# Peripherals.net
KiCad netlist of a schematic drawn in Altium Designer
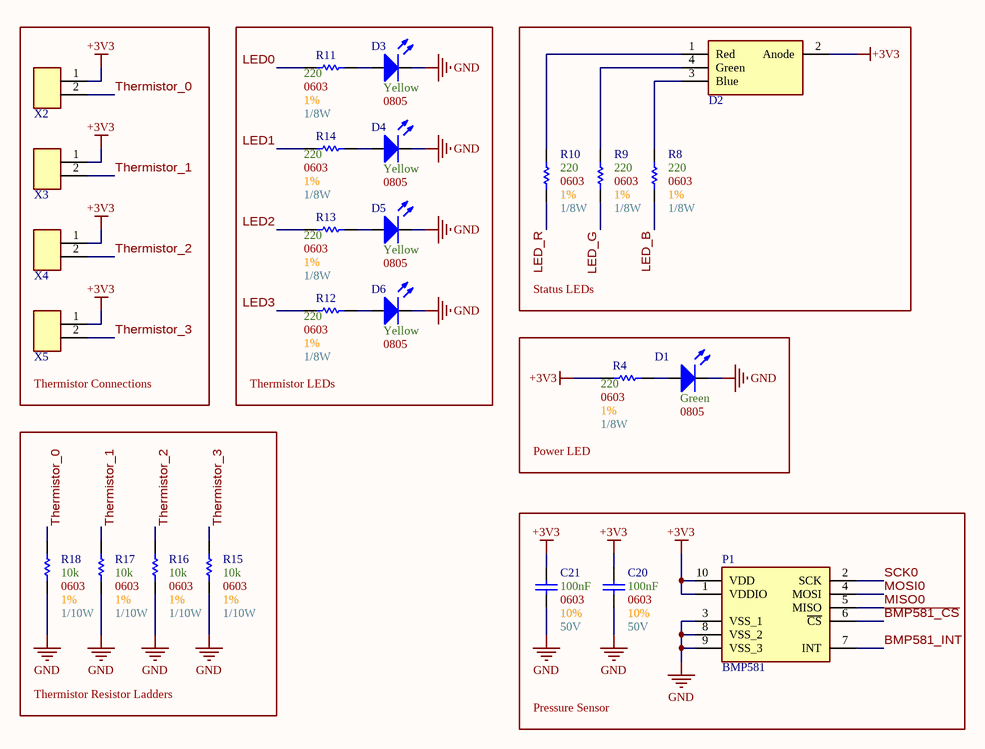
[diagram p0: Peripherals.SchDoc]

(export (version "E")
  (design (tool "Eeschema 10.0.6"))
  (components
    (comp (ref "C20")
      (value "[Cap] 0603 0.1uF 10% 50V")
      (footprint "[Cap] SMD 0603")
      (description "CL10B104KB8NNNC")
      (fields
        (field (name "MAX VOLTAGE") "50V")
        (field (name "SIZE PACKAGE") "0603")
        (field (name "TOLERANCE") "10%")
        (field (name "CAPACITANCE") "100nF")
      )
      (libsource (lib "Capacitors") (part "[Cap] 0603 0.1uF 10% 50V"))
    )
    (comp (ref "C21")
      (value "[Cap] 0603 0.1uF 10% 50V")
      (footprint "[Cap] SMD 0603")
      (description "CL10B104KB8NNNC")
      (fields
        (field (name "MAX VOLTAGE") "50V")
        (field (name "SIZE PACKAGE") "0603")
        (field (name "TOLERANCE") "10%")
        (field (name "CAPACITANCE") "100nF")
      )
      (libsource (lib "Capacitors") (part "[Cap] 0603 0.1uF 10% 50V"))
    )
    (comp (ref "D1")
      (value "[LED] SMD 0805 Green")
      (footprint "[LED] SMD 0805")
      (description "LG R971-KN-1-0-20-R18")
      (fields (field (name "COLOR") "Green") (field (name "SIZE PACKAGE") "0805"))
      (libsource (lib "LEDs") (part "[LED] SMD 0805 Green"))
    )
    (comp (ref "D2")
      (value "[LED] SMD RGB 1.55x1.55mm")
      (footprint "[LED] SMD RGB 1.55x1.55mm")
      (description "LTST-E143EGBW-P1")
      (libsource (lib "LEDs") (part "[LED] SMD RGB 1.55x1.55mm"))
    )
    (comp (ref "D3")
      (value "[LED] SMD 0805 Yellow")
      (footprint "[LED] SMD 0805")
      (description "LY R976-PS-36-0-20-R18")
      (fields (field (name "COLOR") "Yellow") (field (name "SIZE PACKAGE") "0805"))
      (libsource (lib "LEDs") (part "[LED] SMD 0805 Yellow"))
    )
    (comp (ref "D4")
      (value "[LED] SMD 0805 Yellow")
      (footprint "[LED] SMD 0805")
      (description "LY R976-PS-36-0-20-R18")
      (fields (field (name "COLOR") "Yellow") (field (name "SIZE PACKAGE") "0805"))
      (libsource (lib "LEDs") (part "[LED] SMD 0805 Yellow"))
    )
    (comp (ref "D5")
      (value "[LED] SMD 0805 Yellow")
      (footprint "[LED] SMD 0805")
      (description "LY R976-PS-36-0-20-R18")
      (fields (field (name "COLOR") "Yellow") (field (name "SIZE PACKAGE") "0805"))
      (libsource (lib "LEDs") (part "[LED] SMD 0805 Yellow"))
    )
    (comp (ref "D6")
      (value "[LED] SMD 0805 Yellow")
      (footprint "[LED] SMD 0805")
      (description "LY R976-PS-36-0-20-R18")
      (fields (field (name "COLOR") "Yellow") (field (name "SIZE PACKAGE") "0805"))
      (libsource (lib "LEDs") (part "[LED] SMD 0805 Yellow"))
    )
    (comp (ref "P1")
      (value "BMP581")
      (footprint "[Sensor] Barometric Pressure Sensor")
      (libsource (lib "ICs") (part "[Sensor] Barometric Pressure Sensor"))
    )
    (comp (ref "R4")
      (value "[220] SMD 0603 1% 1/10W")
      (footprint "[Res] SMD 0603")
      (description "CRGCQ0805F220R")
      (fields
        (field (name "WATTAGE") "1/8W")
        (field (name "TOLERANCE") "1%")
        (field (name "RESISTANCE") "220")
        (field (name "SIZE PACKAGE") "0603")
      )
      (libsource (lib "Resistors") (part "[220] SMD 0603 1% 1/10W"))
    )
    (comp (ref "R8")
      (value "[220] SMD 0603 1% 1/10W")
      (footprint "[Res] SMD 0603")
      (description "CRGCQ0805F220R")
      (fields
        (field (name "WATTAGE") "1/8W")
        (field (name "TOLERANCE") "1%")
        (field (name "RESISTANCE") "220")
        (field (name "SIZE PACKAGE") "0603")
      )
      (libsource (lib "Resistors") (part "[220] SMD 0603 1% 1/10W"))
    )
    (comp (ref "R9")
      (value "[220] SMD 0603 1% 1/10W")
      (footprint "[Res] SMD 0603")
      (description "CRGCQ0805F220R")
      (fields
        (field (name "WATTAGE") "1/8W")
        (field (name "TOLERANCE") "1%")
        (field (name "RESISTANCE") "220")
        (field (name "SIZE PACKAGE") "0603")
      )
      (libsource (lib "Resistors") (part "[220] SMD 0603 1% 1/10W"))
    )
    (comp (ref "R10")
      (value "[220] SMD 0603 1% 1/10W")
      (footprint "[Res] SMD 0603")
      (description "CRGCQ0805F220R")
      (fields
        (field (name "WATTAGE") "1/8W")
        (field (name "TOLERANCE") "1%")
        (field (name "RESISTANCE") "220")
        (field (name "SIZE PACKAGE") "0603")
      )
      (libsource (lib "Resistors") (part "[220] SMD 0603 1% 1/10W"))
    )
    (comp (ref "R11")
      (value "[220] SMD 0603 1% 1/10W")
      (footprint "[Res] SMD 0603")
      (description "CRGCQ0805F220R")
      (fields
        (field (name "WATTAGE") "1/8W")
        (field (name "TOLERANCE") "1%")
        (field (name "RESISTANCE") "220")
        (field (name "SIZE PACKAGE") "0603")
      )
      (libsource (lib "Resistors") (part "[220] SMD 0603 1% 1/10W"))
    )
    (comp (ref "R12")
      (value "[220] SMD 0603 1% 1/10W")
      (footprint "[Res] SMD 0603")
      (description "CRGCQ0805F220R")
      (fields
        (field (name "WATTAGE") "1/8W")
        (field (name "TOLERANCE") "1%")
        (field (name "RESISTANCE") "220")
        (field (name "SIZE PACKAGE") "0603")
      )
      (libsource (lib "Resistors") (part "[220] SMD 0603 1% 1/10W"))
    )
    (comp (ref "R13")
      (value "[220] SMD 0603 1% 1/10W")
      (footprint "[Res] SMD 0603")
      (description "CRGCQ0805F220R")
      (fields
        (field (name "WATTAGE") "1/8W")
        (field (name "TOLERANCE") "1%")
        (field (name "RESISTANCE") "220")
        (field (name "SIZE PACKAGE") "0603")
      )
      (libsource (lib "Resistors") (part "[220] SMD 0603 1% 1/10W"))
    )
    (comp (ref "R14")
      (value "[220] SMD 0603 1% 1/10W")
      (footprint "[Res] SMD 0603")
      (description "CRGCQ0805F220R")
      (fields
        (field (name "WATTAGE") "1/8W")
        (field (name "TOLERANCE") "1%")
        (field (name "RESISTANCE") "220")
        (field (name "SIZE PACKAGE") "0603")
      )
      (libsource (lib "Resistors") (part "[220] SMD 0603 1% 1/10W"))
    )
    (comp (ref "R15")
      (value "[10k] SMD 0603 1% 1/8W")
      (footprint "[Res] SMD 0603")
      (description "RMCF0603FT10K0")
      (fields
        (field (name "WATTAGE") "1/10W")
        (field (name "TOLERANCE") "1%")
        (field (name "RESISTANCE") "10k")
        (field (name "SIZE PACKAGE") "0603")
      )
      (libsource (lib "Resistors") (part "[10k] SMD 0603 1% 1/8W"))
    )
    (comp (ref "R16")
      (value "[10k] SMD 0603 1% 1/8W")
      (footprint "[Res] SMD 0603")
      (description "RMCF0603FT10K0")
      (fields
        (field (name "WATTAGE") "1/10W")
        (field (name "TOLERANCE") "1%")
        (field (name "RESISTANCE") "10k")
        (field (name "SIZE PACKAGE") "0603")
      )
      (libsource (lib "Resistors") (part "[10k] SMD 0603 1% 1/8W"))
    )
    (comp (ref "R17")
      (value "[10k] SMD 0603 1% 1/8W")
      (footprint "[Res] SMD 0603")
      (description "RMCF0603FT10K0")
      (fields
        (field (name "WATTAGE") "1/10W")
        (field (name "TOLERANCE") "1%")
        (field (name "RESISTANCE") "10k")
        (field (name "SIZE PACKAGE") "0603")
      )
      (libsource (lib "Resistors") (part "[10k] SMD 0603 1% 1/8W"))
    )
    (comp (ref "R18")
      (value "[10k] SMD 0603 1% 1/8W")
      (footprint "[Res] SMD 0603")
      (description "RMCF0603FT10K0")
      (fields
        (field (name "WATTAGE") "1/10W")
        (field (name "TOLERANCE") "1%")
        (field (name "RESISTANCE") "10k")
        (field (name "SIZE PACKAGE") "0603")
      )
      (libsource (lib "Resistors") (part "[10k] SMD 0603 1% 1/8W"))
    )
    (comp (ref "X2")
      (value "[Sherlock] 2pin")
      (footprint "[Sherlock] 2pin")
      (description "0353620250")
      (libsource (lib "Connectors") (part "[Sherlock] 2pin"))
    )
    (comp (ref "X3")
      (value "[Sherlock] 2pin")
      (footprint "[Sherlock] 2pin")
      (description "0353620250")
      (libsource (lib "Connectors") (part "[Sherlock] 2pin"))
    )
    (comp (ref "X4")
      (value "[Sherlock] 2pin")
      (footprint "[Sherlock] 2pin")
      (description "0353620250")
      (libsource (lib "Connectors") (part "[Sherlock] 2pin"))
    )
    (comp (ref "X5")
      (value "[Sherlock] 2pin")
      (footprint "[Sherlock] 2pin")
      (description "0353620250")
      (libsource (lib "Connectors") (part "[Sherlock] 2pin"))
    )
  )
  (nets
    (net (code "1") (name "+3V3") (class "Default")
      (node (ref "C20") (pin "2") (pinfunction "2_2") (pintype "passive"))
      (node (ref "C21") (pin "2") (pinfunction "2_2") (pintype "passive"))
      (node (ref "D2") (pin "2") (pinfunction "Anode_2") (pintype "passive"))
      (node (ref "P1") (pin "1") (pinfunction "VDDIO_1") (pintype "passive"))
      (node (ref "P1") (pin "10") (pinfunction "VDD_10") (pintype "passive"))
      (node (ref "R4") (pin "1") (pinfunction "1_1") (pintype "passive"))
      (node (ref "X2") (pin "1") (pintype "passive"))
      (node (ref "X3") (pin "1") (pintype "passive"))
      (node (ref "X4") (pin "1") (pintype "passive"))
      (node (ref "X5") (pin "1") (pintype "passive"))
    )
    (net (code "2") (name "/BMP581_CS") (class "Default")
      (node (ref "P1") (pin "6") (pinfunction "CS_6") (pintype "passive"))
    )
    (net (code "3") (name "/BMP581_INT") (class "Default")
      (node (ref "P1") (pin "7") (pinfunction "INT_7") (pintype "passive"))
    )
    (net (code "4") (name "/LED0") (class "Default")
      (node (ref "R11") (pin "1") (pinfunction "1_1") (pintype "passive"))
    )
    (net (code "5") (name "/LED1") (class "Default")
      (node (ref "R14") (pin "1") (pinfunction "1_1") (pintype "passive"))
    )
    (net (code "6") (name "/LED2") (class "Default")
      (node (ref "R13") (pin "1") (pinfunction "1_1") (pintype "passive"))
    )
    (net (code "7") (name "/LED3") (class "Default")
      (node (ref "R12") (pin "1") (pinfunction "1_1") (pintype "passive"))
    )
    (net (code "8") (name "/LED_B") (class "Default")
      (node (ref "R8") (pin "1") (pinfunction "1_1") (pintype "passive"))
    )
    (net (code "9") (name "/LED_G") (class "Default")
      (node (ref "R9") (pin "1") (pinfunction "1_1") (pintype "passive"))
    )
    (net (code "10") (name "/LED_R") (class "Default")
      (node (ref "R10") (pin "1") (pinfunction "1_1") (pintype "passive"))
    )
    (net (code "11") (name "/MISO0") (class "Default")
      (node (ref "P1") (pin "5") (pinfunction "MISO_5") (pintype "passive"))
    )
    (net (code "12") (name "/MOSI0") (class "Default")
      (node (ref "P1") (pin "4") (pinfunction "MOSI_4") (pintype "passive"))
    )
    (net (code "13") (name "/SCK0") (class "Default")
      (node (ref "P1") (pin "2") (pinfunction "SCK_2") (pintype "passive"))
    )
    (net (code "14") (name "/Thermistor_0") (class "Default")
      (node (ref "R18") (pin "2") (pinfunction "2_2") (pintype "passive"))
      (node (ref "X2") (pin "2") (pintype "passive"))
    )
    (net (code "15") (name "/Thermistor_1") (class "Default")
      (node (ref "R17") (pin "2") (pinfunction "2_2") (pintype "passive"))
      (node (ref "X3") (pin "2") (pintype "passive"))
    )
    (net (code "16") (name "/Thermistor_2") (class "Default")
      (node (ref "R16") (pin "2") (pinfunction "2_2") (pintype "passive"))
      (node (ref "X4") (pin "2") (pintype "passive"))
    )
    (net (code "17") (name "/Thermistor_3") (class "Default")
      (node (ref "R15") (pin "2") (pinfunction "2_2") (pintype "passive"))
      (node (ref "X5") (pin "2") (pintype "passive"))
    )
    (net (code "18") (name "GND") (class "Default")
      (node (ref "C20") (pin "1") (pinfunction "1_1") (pintype "passive"))
      (node (ref "C21") (pin "1") (pinfunction "1_1") (pintype "passive"))
      (node (ref "D1") (pin "2") (pinfunction "Cathode_2") (pintype "passive"))
      (node (ref "D3") (pin "2") (pinfunction "Cathode_2") (pintype "passive"))
      (node (ref "D4") (pin "2") (pinfunction "Cathode_2") (pintype "passive"))
      (node (ref "D5") (pin "2") (pinfunction "Cathode_2") (pintype "passive"))
      (node (ref "D6") (pin "2") (pinfunction "Cathode_2") (pintype "passive"))
      (node (ref "P1") (pin "3") (pinfunction "VSS_1_3") (pintype "passive"))
      (node (ref "P1") (pin "8") (pinfunction "VSS_2_8") (pintype "passive"))
      (node (ref "P1") (pin "9") (pinfunction "VSS_3_9") (pintype "passive"))
      (node (ref "R15") (pin "1") (pinfunction "1_1") (pintype "passive"))
      (node (ref "R16") (pin "1") (pinfunction "1_1") (pintype "passive"))
      (node (ref "R17") (pin "1") (pinfunction "1_1") (pintype "passive"))
      (node (ref "R18") (pin "1") (pinfunction "1_1") (pintype "passive"))
    )
    (net (code "19") (name "Net-(D1-Anode)") (class "Default")
      (node (ref "D1") (pin "1") (pinfunction "Anode_1") (pintype "passive"))
      (node (ref "R4") (pin "2") (pinfunction "2_2") (pintype "passive"))
    )
    (net (code "20") (name "Net-(D2-Blue)") (class "Default")
      (node (ref "D2") (pin "3") (pinfunction "Blue_3") (pintype "passive"))
      (node (ref "R8") (pin "2") (pinfunction "2_2") (pintype "passive"))
    )
    (net (code "21") (name "Net-(D2-Green)") (class "Default")
      (node (ref "D2") (pin "4") (pinfunction "Green_4") (pintype "passive"))
      (node (ref "R9") (pin "2") (pinfunction "2_2") (pintype "passive"))
    )
    (net (code "22") (name "Net-(D2-Red)") (class "Default")
      (node (ref "D2") (pin "1") (pinfunction "Red_1") (pintype "passive"))
      (node (ref "R10") (pin "2") (pinfunction "2_2") (pintype "passive"))
    )
    (net (code "23") (name "Net-(D3-Anode)") (class "Default")
      (node (ref "D3") (pin "1") (pinfunction "Anode_1") (pintype "passive"))
      (node (ref "R11") (pin "2") (pinfunction "2_2") (pintype "passive"))
    )
    (net (code "24") (name "Net-(D4-Anode)") (class "Default")
      (node (ref "D4") (pin "1") (pinfunction "Anode_1") (pintype "passive"))
      (node (ref "R14") (pin "2") (pinfunction "2_2") (pintype "passive"))
    )
    (net (code "25") (name "Net-(D5-Anode)") (class "Default")
      (node (ref "D5") (pin "1") (pinfunction "Anode_1") (pintype "passive"))
      (node (ref "R13") (pin "2") (pinfunction "2_2") (pintype "passive"))
    )
    (net (code "26") (name "Net-(D6-Anode)") (class "Default")
      (node (ref "D6") (pin "1") (pinfunction "Anode_1") (pintype "passive"))
      (node (ref "R12") (pin "2") (pinfunction "2_2") (pintype "passive"))
    )
  )
)
